# buck_converter.net
KiCad netlist of a schematic drawn in EAGLE
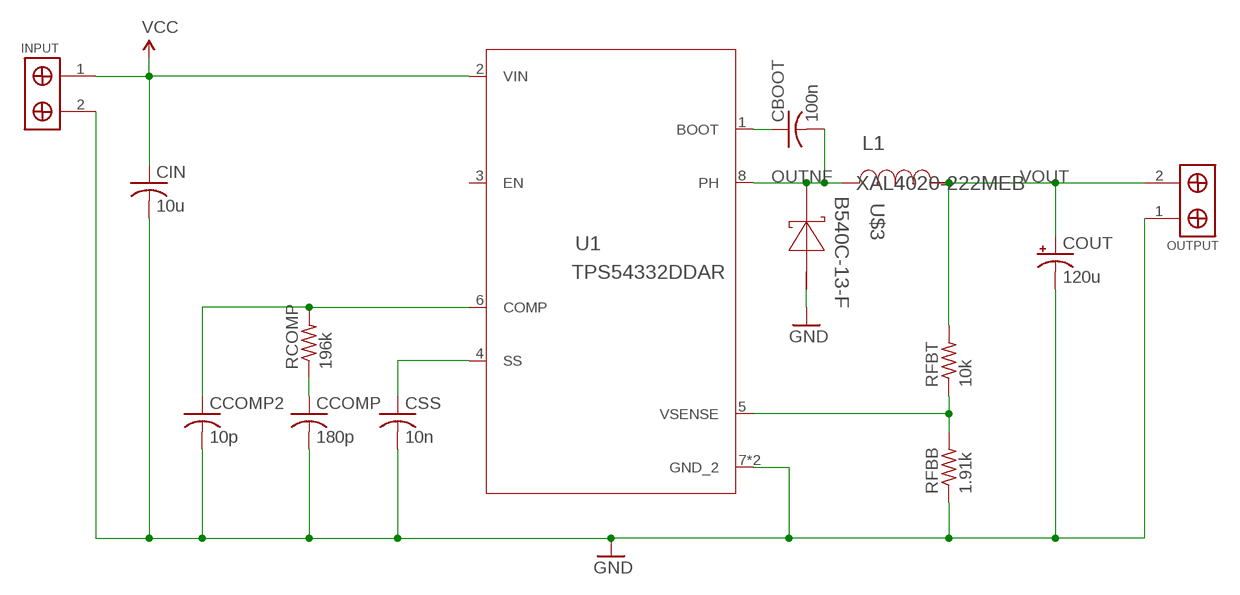
[diagram p0: schematic, sheet 1]

(export (version "E")
  (design (tool "Eeschema 10.0.6"))
  (components
    (comp (ref "CBOOT")
      (value "100n")
      (footprint "eagle-import:C0805")
      (libsource (lib "eagle-import") (part "C-USC0805"))
    )
    (comp (ref "CCOMP")
      (value "180p")
      (footprint "eagle-import:C0805")
      (libsource (lib "eagle-import") (part "C-USC0805"))
    )
    (comp (ref "CCOMP2")
      (value "10p")
      (footprint "eagle-import:C0805")
      (libsource (lib "eagle-import") (part "C-USC0805"))
    )
    (comp (ref "CIN")
      (value "10u")
      (footprint "eagle-import:C1210")
      (libsource (lib "eagle-import") (part "C-USC1210"))
    )
    (comp (ref "COUT")
      (value "120u")
      (footprint "eagle-import:D_7343-31R")
      (libsource (lib "eagle-import") (part "CPOL-USD/7343-31R"))
    )
    (comp (ref "CSS")
      (value "10n")
      (footprint "eagle-import:C0805")
      (libsource (lib "eagle-import") (part "C-USC0805"))
    )
    (comp (ref "INPUT")
      (value "SCREW_TERMINALS")
      (footprint "eagle-import:1X02-5MM")
      (libsource (lib "eagle-import") (part "SCREW_TERMINALS"))
    )
    (comp (ref "L1")
      (value "XAL4020-222MEB")
      (footprint "eagle-import:XAL4020")
      (libsource (lib "eagle-import") (part "XAL4020-222MEB"))
    )
    (comp (ref "OUTPUT")
      (value "SCREW_TERMINALS")
      (footprint "eagle-import:1X02-5MM")
      (libsource (lib "eagle-import") (part "SCREW_TERMINALS"))
    )
    (comp (ref "RCOMP")
      (value "196k")
      (footprint "eagle-import:R0805")
      (libsource (lib "eagle-import") (part "R-US_R0805"))
    )
    (comp (ref "RFBB")
      (value "1.91k")
      (footprint "eagle-import:R0805")
      (libsource (lib "eagle-import") (part "R-US_R0805"))
    )
    (comp (ref "RFBT")
      (value "10k")
      (footprint "eagle-import:R0805")
      (libsource (lib "eagle-import") (part "R-US_R0805"))
    )
    (comp (ref "U$3")
      (value "B540C-13-F")
      (footprint "eagle-import:SMC")
      (libsource (lib "eagle-import") (part "B540C-13-F"))
    )
    (comp (ref "U1")
      (value "TPS54332DDAR")
      (footprint "eagle-import:DDA0008H")
      (libsource (lib "eagle-import") (part "TPS54332DDAR"))
    )
  )
  (nets
    (net (code "1") (name "/OUTNF") (class "Default")
      (node (ref "CBOOT") (pin "2") (pinfunction "2_2") (pintype "passive"))
      (node (ref "L1") (pin "1") (pinfunction "1_1") (pintype "passive"))
      (node (ref "U$3") (pin "1") (pinfunction "K_1") (pintype "passive"))
      (node (ref "U1") (pin "8") (pinfunction "PH_8") (pintype "passive"))
    )
    (net (code "2") (name "/VOUT") (class "Default")
      (node (ref "COUT") (pin "+") (pinfunction "+_+") (pintype "passive"))
      (node (ref "L1") (pin "2") (pinfunction "2_2") (pintype "passive"))
      (node (ref "OUTPUT") (pin "2") (pinfunction "2_2") (pintype "input"))
      (node (ref "RFBT") (pin "2") (pinfunction "2_2") (pintype "passive"))
    )
    (net (code "3") (name "GND") (class "Default")
      (node (ref "CCOMP") (pin "2") (pinfunction "2_2") (pintype "passive"))
      (node (ref "CCOMP2") (pin "2") (pinfunction "2_2") (pintype "passive"))
      (node (ref "CIN") (pin "2") (pinfunction "2_2") (pintype "passive"))
      (node (ref "COUT") (pin "-") (pinfunction "-_-") (pintype "passive"))
      (node (ref "CSS") (pin "2") (pinfunction "2_2") (pintype "passive"))
      (node (ref "INPUT") (pin "2") (pinfunction "2_2") (pintype "input"))
      (node (ref "OUTPUT") (pin "1") (pinfunction "1_1") (pintype "input"))
      (node (ref "RFBB") (pin "1") (pinfunction "1_1") (pintype "passive"))
      (node (ref "U$3") (pin "2") (pinfunction "A_2") (pintype "passive"))
      (node (ref "U1") (pin "7") (pinfunction "GND_2_7") (pintype "passive"))
      (node (ref "U1") (pin "9") (pinfunction "GND_2_9") (pintype "passive"))
    )
    (net (code "4") (name "Net-(CCOMP-Pad1)") (class "Default")
      (node (ref "CCOMP") (pin "1") (pinfunction "1_1") (pintype "passive"))
      (node (ref "RCOMP") (pin "1") (pinfunction "1_1") (pintype "passive"))
    )
    (net (code "5") (name "Net-(U1-BOOT)") (class "Default")
      (node (ref "CBOOT") (pin "1") (pinfunction "1_1") (pintype "passive"))
      (node (ref "U1") (pin "1") (pinfunction "BOOT_1") (pintype "passive"))
    )
    (net (code "6") (name "Net-(U1-COMP)") (class "Default")
      (node (ref "CCOMP2") (pin "1") (pinfunction "1_1") (pintype "passive"))
      (node (ref "RCOMP") (pin "2") (pinfunction "2_2") (pintype "passive"))
      (node (ref "U1") (pin "6") (pinfunction "COMP_6") (pintype "passive"))
    )
    (net (code "7") (name "Net-(U1-SS)") (class "Default")
      (node (ref "CSS") (pin "1") (pinfunction "1_1") (pintype "passive"))
      (node (ref "U1") (pin "4") (pinfunction "SS_4") (pintype "passive"))
    )
    (net (code "8") (name "Net-(U1-VSENSE)") (class "Default")
      (node (ref "RFBB") (pin "2") (pinfunction "2_2") (pintype "passive"))
      (node (ref "RFBT") (pin "1") (pinfunction "1_1") (pintype "passive"))
      (node (ref "U1") (pin "5") (pinfunction "VSENSE_5") (pintype "passive"))
    )
    (net (code "9") (name "VCC") (class "Default")
      (node (ref "CIN") (pin "1") (pinfunction "1_1") (pintype "passive"))
      (node (ref "INPUT") (pin "1") (pinfunction "1_1") (pintype "input"))
      (node (ref "U1") (pin "2") (pinfunction "VIN_2") (pintype "passive"))
    )
    (net (code "10") (name "unconnected-(U1-EN-Pad3)") (class "Default")
      (node (ref "U1") (pin "3") (pinfunction "EN_3") (pintype "passive"))
    )
  )
)
